# cell.net
KiCad netlist of a schematic drawn in EAGLE
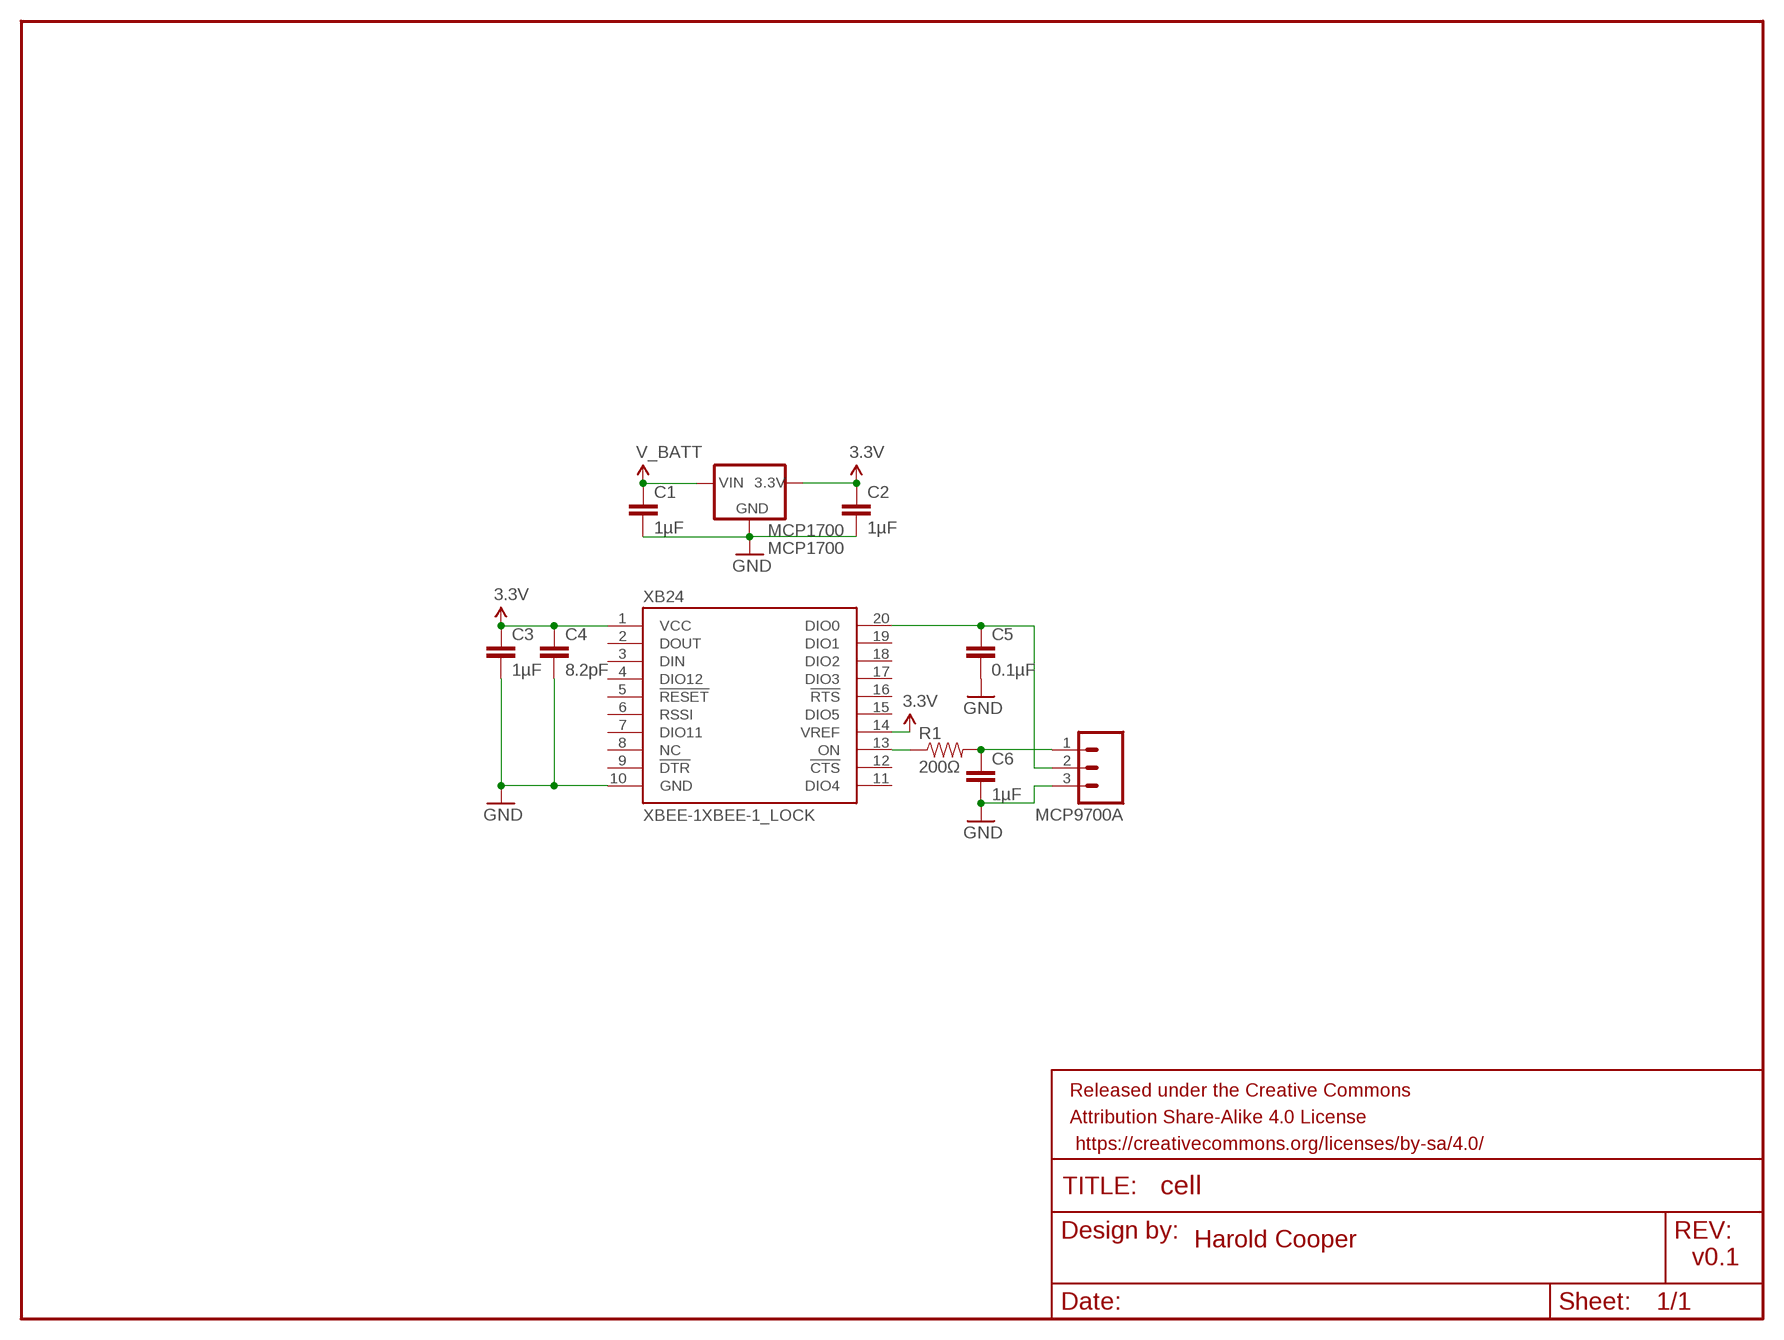
[diagram p0: schematic, sheet 1]

(export (version "E")
  (design (tool "Eeschema 10.0.6"))
  (components
    (comp (ref "C1")
      (value "1µF")
      (footprint "eagle-import:0805")
      (libsource (lib "eagle-import") (part "CAP0805"))
    )
    (comp (ref "C2")
      (value "1µF")
      (footprint "eagle-import:0805")
      (libsource (lib "eagle-import") (part "CAP0805"))
    )
    (comp (ref "C3")
      (value "1µF")
      (footprint "eagle-import:0805")
      (libsource (lib "eagle-import") (part "CAP0805"))
    )
    (comp (ref "C4")
      (value "8.2pF")
      (footprint "eagle-import:0805")
      (libsource (lib "eagle-import") (part "CAP0805"))
    )
    (comp (ref "C5")
      (value "0.1µF")
      (footprint "eagle-import:0805")
      (libsource (lib "eagle-import") (part "CAP0805"))
    )
    (comp (ref "C6")
      (value "1µF")
      (footprint "eagle-import:0805")
      (libsource (lib "eagle-import") (part "CAP0805"))
    )
    (comp (ref "FRAME1")
      (value "FRAME-LETTER")
      (footprint "eagle-import:CREATIVE_COMMONS")
      (libsource (lib "eagle-import") (part "FRAME-LETTER"))
    )
    (comp (ref "MCP1700")
      (value "MCP1700")
      (footprint "eagle-import:SOT-89-3")
      (libsource (lib "eagle-import") (part "MCP1700"))
    )
    (comp (ref "MCP9700A")
      (value "M03LOCK")
      (footprint "eagle-import:1X03_LOCK")
      (libsource (lib "eagle-import") (part "M03LOCK"))
    )
    (comp (ref "R1")
      (value "200Ω")
      (footprint "eagle-import:0805")
      (libsource (lib "eagle-import") (part "RESISTOR0805-RES"))
    )
    (comp (ref "XB24")
      (value "XBEE-1XBEE-1_LOCK")
      (footprint "eagle-import:XBEE-1_LOCK")
      (libsource (lib "eagle-import") (part "XBEE-1XBEE-1_LOCK"))
    )
  )
  (nets
    (net (code "1") (name "3.3V") (class "Default")
      (node (ref "C2") (pin "1") (pinfunction "1_1") (pintype "passive"))
      (node (ref "C3") (pin "1") (pinfunction "1_1") (pintype "passive"))
      (node (ref "C4") (pin "1") (pinfunction "1_1") (pintype "passive"))
      (node (ref "MCP1700") (pin "3") (pinfunction "3.3V_3") (pintype "output"))
      (node (ref "XB24") (pin "1") (pinfunction "VCC_1") (pintype "power_in"))
      (node (ref "XB24") (pin "14") (pinfunction "VREF_14") (pintype "power_in"))
    )
    (net (code "2") (name "GND") (class "Default")
      (node (ref "C1") (pin "2") (pinfunction "2_2") (pintype "passive"))
      (node (ref "C2") (pin "2") (pinfunction "2_2") (pintype "passive"))
      (node (ref "C3") (pin "2") (pinfunction "2_2") (pintype "passive"))
      (node (ref "C4") (pin "2") (pinfunction "2_2") (pintype "passive"))
      (node (ref "C5") (pin "2") (pinfunction "2_2") (pintype "passive"))
      (node (ref "C6") (pin "2") (pinfunction "2_2") (pintype "passive"))
      (node (ref "MCP1700") (pin "1") (pinfunction "GND_1") (pintype "power_in"))
      (node (ref "MCP9700A") (pin "3") (pinfunction "3_3") (pintype "passive"))
      (node (ref "XB24") (pin "10") (pinfunction "GND_10") (pintype "power_in"))
    )
    (net (code "3") (name "Net-(C6-Pad1)") (class "Default")
      (node (ref "C6") (pin "1") (pinfunction "1_1") (pintype "passive"))
      (node (ref "MCP9700A") (pin "1") (pinfunction "1_1") (pintype "passive"))
      (node (ref "R1") (pin "2") (pinfunction "2_2") (pintype "passive"))
    )
    (net (code "4") (name "Net-(XB24-DIO0)") (class "Default")
      (node (ref "C5") (pin "1") (pinfunction "1_1") (pintype "passive"))
      (node (ref "MCP9700A") (pin "2") (pinfunction "2_2") (pintype "passive"))
      (node (ref "XB24") (pin "20") (pinfunction "DIO0_20") (pintype "bidirectional"))
    )
    (net (code "5") (name "Net-(XB24-ON)") (class "Default")
      (node (ref "R1") (pin "1") (pinfunction "1_1") (pintype "passive"))
      (node (ref "XB24") (pin "13") (pinfunction "ON_13") (pintype "bidirectional"))
    )
    (net (code "6") (name "V_BATT") (class "Default")
      (node (ref "C1") (pin "1") (pinfunction "1_1") (pintype "passive"))
      (node (ref "MCP1700") (pin "2") (pinfunction "IN_2") (pintype "power_in"))
    )
    (net (code "7") (name "unconnected-(XB24-DIN-Pad3)") (class "Default")
      (node (ref "XB24") (pin "3") (pinfunction "DIN_3") (pintype "input"))
    )
    (net (code "8") (name "unconnected-(XB24-DIO1-Pad19)") (class "Default")
      (node (ref "XB24") (pin "19") (pinfunction "DIO1_19") (pintype "bidirectional"))
    )
    (net (code "9") (name "unconnected-(XB24-DIO2-Pad18)") (class "Default")
      (node (ref "XB24") (pin "18") (pinfunction "DIO2_18") (pintype "bidirectional"))
    )
    (net (code "10") (name "unconnected-(XB24-DIO3-Pad17)") (class "Default")
      (node (ref "XB24") (pin "17") (pinfunction "DIO3_17") (pintype "bidirectional"))
    )
    (net (code "11") (name "unconnected-(XB24-DIO4-Pad11)") (class "Default")
      (node (ref "XB24") (pin "11") (pinfunction "DIO4_11") (pintype "bidirectional"))
    )
    (net (code "12") (name "unconnected-(XB24-DIO5-Pad15)") (class "Default")
      (node (ref "XB24") (pin "15") (pinfunction "DIO5_15") (pintype "bidirectional"))
    )
    (net (code "13") (name "unconnected-(XB24-DIO11-Pad7)") (class "Default")
      (node (ref "XB24") (pin "7") (pinfunction "DIO11_7") (pintype "bidirectional"))
    )
    (net (code "14") (name "unconnected-(XB24-DIO12-Pad4)") (class "Default")
      (node (ref "XB24") (pin "4") (pinfunction "DIO12_4") (pintype "bidirectional"))
    )
    (net (code "15") (name "unconnected-(XB24-DOUT-Pad2)") (class "Default")
      (node (ref "XB24") (pin "2") (pinfunction "DOUT_2") (pintype "output"))
    )
    (net (code "16") (name "unconnected-(XB24-NC-Pad8)") (class "Default")
      (node (ref "XB24") (pin "8") (pinfunction "NC_8") (pintype "no_connect"))
    )
    (net (code "17") (name "unconnected-(XB24-RSSI-Pad6)") (class "Default")
      (node (ref "XB24") (pin "6") (pinfunction "RSSI_6") (pintype "bidirectional"))
    )
    (net (code "18") (name "unconnected-(XB24-~{CTS}-Pad12)") (class "Default")
      (node (ref "XB24") (pin "12") (pinfunction "~{CTS}_12") (pintype "output"))
    )
    (net (code "19") (name "unconnected-(XB24-~{DTR}-Pad9)") (class "Default")
      (node (ref "XB24") (pin "9") (pinfunction "~{DTR}_9") (pintype "bidirectional"))
    )
    (net (code "20") (name "unconnected-(XB24-~{RESET}-Pad5)") (class "Default")
      (node (ref "XB24") (pin "5") (pinfunction "~{RESET}_5") (pintype "input"))
    )
    (net (code "21") (name "unconnected-(XB24-~{RTS}-Pad16)") (class "Default")
      (node (ref "XB24") (pin "16") (pinfunction "~{RTS}_16") (pintype "input"))
    )
  )
)
